# 01_FPGA_FlashMem.net
KiCad netlist of a schematic drawn in Altium Designer
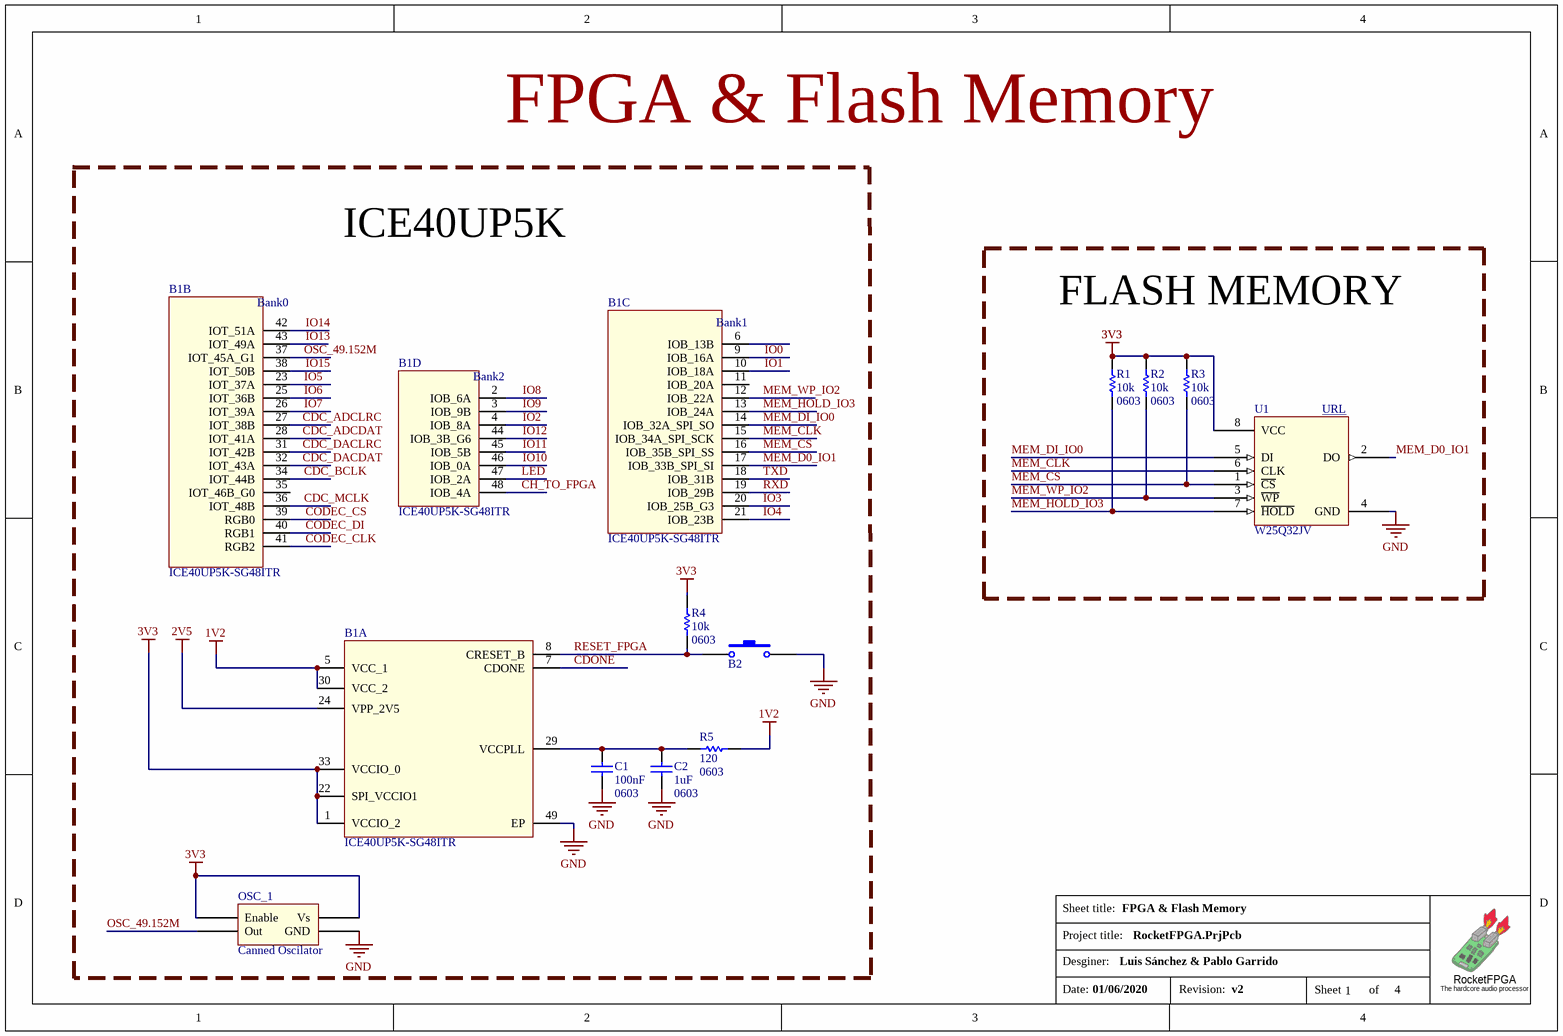
[diagram p0: 01_FPGA_FlashMem.SchDoc]

(export (version "E")
  (design (tool "Eeschema 10.0.6"))
  (components
    (comp (ref "B1")
      (value "ICE40UP5K-SG48ITR")
      (footprint "QFN50P700X700X100-49N-D")
      (description "FPGA - Field Programmable Gate Array iCE40-UltraPlus, 5280 LUTs, 1.2V")
      (libsource (lib "") (part "ICE40UP5K-SG48ITR_1"))
    )
    (comp (ref "B2")
      (value "FSM6JH")
      (footprint "SMD_PUSHBUTTON_3x6x2mm5")
      (description "Button THT Switch")
      (libsource (lib "RocketFPGA") (part "FSM6JH"))
    )
    (comp (ref "C1")
      (value "100nF")
      (footprint "0603 CAP")
      (description "Capacitor")
      (fields (field (name "PACKAGE") "0603") (field (name "Comment") "Ceramic capacitor"))
      (libsource (lib "RocketFPGA") (part "Capacitor"))
    )
    (comp (ref "C2")
      (value "1uF")
      (footprint "0603 CAP")
      (description "Capacitor")
      (fields (field (name "PACKAGE") "0603") (field (name "Comment") "Ceramic capacitor"))
      (libsource (lib "RocketFPGA") (part "Capacitor"))
    )
    (comp (ref "OSC_1")
      (value "Canned Oscilator")
      (footprint "canned oscillator small")
      (description "Canned Oscilator -LFSPXO019116BULK")
      (libsource (lib "RocketFPGA") (part "Canned Oscilator"))
    )
    (comp (ref "R1")
      (value "10k")
      (footprint "Resistencia 0603")
      (description "Resistor")
      (fields (field (name "PACKAGE") "0603"))
      (libsource (lib "RocketFPGA") (part "Resistor"))
    )
    (comp (ref "R2")
      (value "10k")
      (footprint "Resistencia 0603")
      (description "Resistor")
      (fields (field (name "PACKAGE") "0603"))
      (libsource (lib "RocketFPGA") (part "Resistor"))
    )
    (comp (ref "R3")
      (value "10k")
      (footprint "Resistencia 0603")
      (description "Resistor")
      (fields (field (name "PACKAGE") "0603"))
      (libsource (lib "RocketFPGA") (part "Resistor"))
    )
    (comp (ref "R4")
      (value "10k")
      (footprint "Resistencia 0603")
      (description "Resistor")
      (fields (field (name "PACKAGE") "0603"))
      (libsource (lib "RocketFPGA") (part "Resistor"))
    )
    (comp (ref "R5")
      (value "120")
      (footprint "Resistencia 0603")
      (description "Resistor")
      (fields (field (name "PACKAGE") "0603"))
      (libsource (lib "RocketFPGA") (part "Resistor"))
    )
    (comp (ref "U1")
      (value "W25Q32JV")
      (footprint "W25Q32J")
      (description "32M-BIT SERIAL FLASH MEMORY WITH DUAL AND QUAD SPI")
      (libsource (lib "RocketFPGA") (part "W25Q32JV"))
    )
  )
  (nets
    (net (code "1") (name "/CDC_ADCDAT") (class "Default")
      (node (ref "B1") (pin "28") (pinfunction "IOT_41A_28") (pintype "passive"))
    )
    (net (code "2") (name "/CDC_ADCLRC") (class "Default")
      (node (ref "B1") (pin "27") (pinfunction "IOT_38B_27") (pintype "passive"))
    )
    (net (code "3") (name "/CDC_BCLK") (class "Default")
      (node (ref "B1") (pin "34") (pinfunction "IOT_44B_34") (pintype "passive"))
    )
    (net (code "4") (name "/CDC_DACDAT") (class "Default")
      (node (ref "B1") (pin "32") (pinfunction "IOT_43A_32") (pintype "passive"))
    )
    (net (code "5") (name "/CDC_DACLRC") (class "Default")
      (node (ref "B1") (pin "31") (pinfunction "IOT_42B_31") (pintype "passive"))
    )
    (net (code "6") (name "/CDC_MCLK") (class "Default")
      (node (ref "B1") (pin "36") (pinfunction "IOT_48B_36") (pintype "passive"))
    )
    (net (code "7") (name "/CDONE") (class "Default")
      (node (ref "B1") (pin "7") (pinfunction "CDONE_7") (pintype "passive"))
    )
    (net (code "8") (name "/CH_TO_FPGA") (class "Default")
      (node (ref "B1") (pin "48") (pinfunction "IOB_4A_48") (pintype "passive"))
    )
    (net (code "9") (name "/CODEC_CLK") (class "Default")
      (node (ref "B1") (pin "41") (pinfunction "RGB2_41") (pintype "passive"))
    )
    (net (code "10") (name "/CODEC_CS") (class "Default")
      (node (ref "B1") (pin "39") (pinfunction "RGB0_39") (pintype "passive"))
    )
    (net (code "11") (name "/CODEC_DI") (class "Default")
      (node (ref "B1") (pin "40") (pinfunction "RGB1_40") (pintype "passive"))
    )
    (net (code "12") (name "/IO0") (class "Default")
      (node (ref "B1") (pin "9") (pinfunction "IOB_16A_9") (pintype "passive"))
    )
    (net (code "13") (name "/IO1") (class "Default")
      (node (ref "B1") (pin "10") (pinfunction "IOB_18A_10") (pintype "passive"))
    )
    (net (code "14") (name "/IO2") (class "Default")
      (node (ref "B1") (pin "4") (pinfunction "IOB_8A_4") (pintype "passive"))
    )
    (net (code "15") (name "/IO3") (class "Default")
      (node (ref "B1") (pin "20") (pinfunction "IOB_25B_G3_20") (pintype "passive"))
    )
    (net (code "16") (name "/IO4") (class "Default")
      (node (ref "B1") (pin "21") (pinfunction "IOB_23B_21") (pintype "passive"))
    )
    (net (code "17") (name "/IO5") (class "Default")
      (node (ref "B1") (pin "23") (pinfunction "IOT_37A_23") (pintype "passive"))
    )
    (net (code "18") (name "/IO6") (class "Default")
      (node (ref "B1") (pin "25") (pinfunction "IOT_36B_25") (pintype "passive"))
    )
    (net (code "19") (name "/IO7") (class "Default")
      (node (ref "B1") (pin "26") (pinfunction "IOT_39A_26") (pintype "passive"))
    )
    (net (code "20") (name "/IO8") (class "Default")
      (node (ref "B1") (pin "2") (pinfunction "IOB_6A_2") (pintype "passive"))
    )
    (net (code "21") (name "/IO9") (class "Default")
      (node (ref "B1") (pin "3") (pinfunction "IOB_9B_3") (pintype "passive"))
    )
    (net (code "22") (name "/IO10") (class "Default")
      (node (ref "B1") (pin "46") (pinfunction "IOB_0A_46") (pintype "passive"))
    )
    (net (code "23") (name "/IO11") (class "Default")
      (node (ref "B1") (pin "45") (pinfunction "IOB_5B_45") (pintype "passive"))
    )
    (net (code "24") (name "/IO12") (class "Default")
      (node (ref "B1") (pin "44") (pinfunction "IOB_3B_G6_44") (pintype "passive"))
    )
    (net (code "25") (name "/IO13") (class "Default")
      (node (ref "B1") (pin "43") (pinfunction "IOT_49A_43") (pintype "passive"))
    )
    (net (code "26") (name "/IO14") (class "Default")
      (node (ref "B1") (pin "42") (pinfunction "IOT_51A_42") (pintype "passive"))
    )
    (net (code "27") (name "/IO15") (class "Default")
      (node (ref "B1") (pin "38") (pinfunction "IOT_50B_38") (pintype "passive"))
    )
    (net (code "28") (name "/LED") (class "Default")
      (node (ref "B1") (pin "47") (pinfunction "IOB_2A_47") (pintype "passive"))
    )
    (net (code "29") (name "/MEM_CLK") (class "Default")
      (node (ref "B1") (pin "15") (pinfunction "IOB_34A_SPI_SCK_15") (pintype "passive"))
      (node (ref "U1") (pin "6") (pinfunction "CLK_6") (pintype "input"))
    )
    (net (code "30") (name "/MEM_CS") (class "Default")
      (node (ref "B1") (pin "16") (pinfunction "IOB_35B_SPI_SS_16") (pintype "passive"))
      (node (ref "R3") (pin "1") (pinfunction "1_1") (pintype "passive"))
      (node (ref "U1") (pin "1") (pinfunction "~{CS}_1") (pintype "input"))
    )
    (net (code "31") (name "/MEM_D0_IO1") (class "Default")
      (node (ref "B1") (pin "17") (pinfunction "IOB_33B_SPI_SI_17") (pintype "passive"))
      (node (ref "U1") (pin "2") (pinfunction "DO_2") (pintype "output"))
    )
    (net (code "32") (name "/MEM_DI_IO0") (class "Default")
      (node (ref "B1") (pin "14") (pinfunction "IOB_32A_SPI_SO_14") (pintype "passive"))
      (node (ref "U1") (pin "5") (pinfunction "DI_5") (pintype "input"))
    )
    (net (code "33") (name "/MEM_HOLD_IO3") (class "Default")
      (node (ref "B1") (pin "13") (pinfunction "IOB_24A_13") (pintype "passive"))
      (node (ref "R1") (pin "1") (pinfunction "1_1") (pintype "passive"))
      (node (ref "U1") (pin "7") (pinfunction "~{HOLD}_7") (pintype "input"))
    )
    (net (code "34") (name "/MEM_WP_IO2") (class "Default")
      (node (ref "B1") (pin "12") (pinfunction "IOB_22A_12") (pintype "passive"))
      (node (ref "R2") (pin "1") (pinfunction "1_1") (pintype "passive"))
      (node (ref "U1") (pin "3") (pinfunction "~{WP}_3") (pintype "input"))
    )
    (net (code "35") (name "/OSC_49.152M") (class "Default")
      (node (ref "B1") (pin "37") (pinfunction "IOT_45A_G1_37") (pintype "passive"))
      (node (ref "OSC_1") (pin "3") (pinfunction "Out_3") (pintype "passive"))
    )
    (net (code "36") (name "/RESET_FPGA") (class "Default")
      (node (ref "B1") (pin "8") (pinfunction "CRESET_B_8") (pintype "passive"))
      (node (ref "B2") (pin "1") (pinfunction "1_1") (pintype "passive"))
      (node (ref "R4") (pin "1") (pinfunction "1_1") (pintype "passive"))
    )
    (net (code "37") (name "/RXD") (class "Default")
      (node (ref "B1") (pin "19") (pinfunction "IOB_29B_19") (pintype "passive"))
    )
    (net (code "38") (name "/TXD") (class "Default")
      (node (ref "B1") (pin "18") (pinfunction "IOB_31B_18") (pintype "passive"))
    )
    (net (code "39") (name "1V2") (class "Default")
      (node (ref "B1") (pin "30") (pinfunction "VCC_2_30") (pintype "passive"))
      (node (ref "B1") (pin "5") (pinfunction "VCC_1_5") (pintype "passive"))
      (node (ref "R5") (pin "2") (pinfunction "2_2") (pintype "passive"))
    )
    (net (code "40") (name "2V5") (class "Default")
      (node (ref "B1") (pin "24") (pinfunction "VPP_2V5_24") (pintype "passive"))
    )
    (net (code "41") (name "3V3") (class "Default")
      (node (ref "B1") (pin "1") (pinfunction "VCCIO_2_1") (pintype "passive"))
      (node (ref "B1") (pin "22") (pinfunction "SPI_VCCIO1_22") (pintype "passive"))
      (node (ref "B1") (pin "33") (pinfunction "VCCIO_0_33") (pintype "passive"))
      (node (ref "OSC_1") (pin "1") (pinfunction "Enable_1") (pintype "passive"))
      (node (ref "OSC_1") (pin "4") (pinfunction "Vs_4") (pintype "passive"))
      (node (ref "R1") (pin "2") (pinfunction "2_2") (pintype "passive"))
      (node (ref "R2") (pin "2") (pinfunction "2_2") (pintype "passive"))
      (node (ref "R3") (pin "2") (pinfunction "2_2") (pintype "passive"))
      (node (ref "R4") (pin "2") (pinfunction "2_2") (pintype "passive"))
      (node (ref "U1") (pin "8") (pinfunction "VCC_8") (pintype "power_in"))
    )
    (net (code "42") (name "GND") (class "Default")
      (node (ref "B1") (pin "49") (pinfunction "EP_49") (pintype "passive"))
      (node (ref "B2") (pin "2") (pinfunction "2_2") (pintype "passive"))
      (node (ref "C1") (pin "1") (pinfunction "1_1") (pintype "passive"))
      (node (ref "C2") (pin "1") (pinfunction "1_1") (pintype "passive"))
      (node (ref "OSC_1") (pin "2") (pinfunction "GND_2") (pintype "passive"))
      (node (ref "U1") (pin "4") (pinfunction "GND_4") (pintype "power_in"))
    )
    (net (code "43") (name "Net-(B1A-VCCPLL)") (class "Default")
      (node (ref "B1") (pin "29") (pinfunction "VCCPLL_29") (pintype "passive"))
      (node (ref "C1") (pin "2") (pinfunction "2_2") (pintype "passive"))
      (node (ref "C2") (pin "2") (pinfunction "2_2") (pintype "passive"))
      (node (ref "R5") (pin "1") (pinfunction "1_1") (pintype "passive"))
    )
    (net (code "44") (name "unconnected-(B1B-IOT_46B_G0-Pad35)") (class "Default")
      (node (ref "B1") (pin "35") (pinfunction "IOT_46B_G0_35") (pintype "passive"))
    )
    (net (code "45") (name "unconnected-(B1C-IOB_13B-Pad6)") (class "Default")
      (node (ref "B1") (pin "6") (pinfunction "IOB_13B_6") (pintype "passive"))
    )
    (net (code "46") (name "unconnected-(B1C-IOB_20A-Pad11)") (class "Default")
      (node (ref "B1") (pin "11") (pinfunction "IOB_20A_11") (pintype "passive"))
    )
  )
)
